# misc.net
KiCad netlist of a schematic drawn in Altium Designer
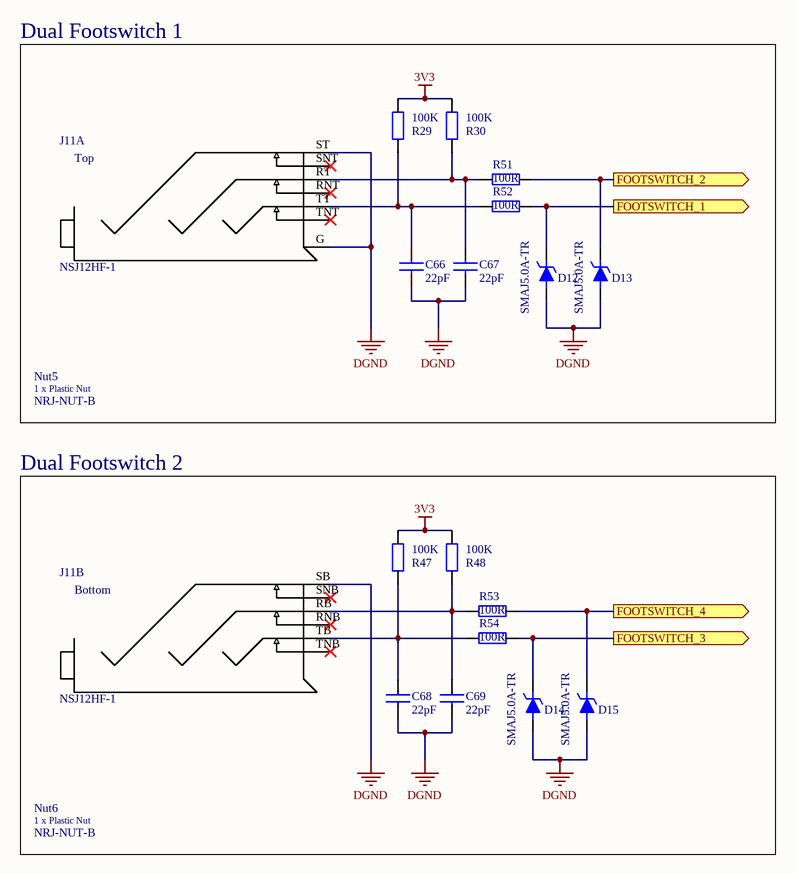
[diagram p0: misc.SchDoc]

(export (version "E")
  (design (tool "Eeschema 10.0.6"))
  (components
    (comp (ref "C66")
      (value "22pF")
      (footprint "SM/C_0603")
      (description "Capacitor, ceramic")
      (fields (field (name "MANUFACTURER") "Kemet ") (field (name "VOLTAGE") "50V"))
      (libsource (lib "Database_heig-vd") (part "Cap"))
    )
    (comp (ref "C67")
      (value "22pF")
      (footprint "SM/C_0603")
      (description "Capacitor, ceramic")
      (fields (field (name "MANUFACTURER") "Kemet ") (field (name "VOLTAGE") "50V"))
      (libsource (lib "Database_heig-vd") (part "Cap"))
    )
    (comp (ref "C68")
      (value "22pF")
      (footprint "SM/C_0603")
      (description "Capacitor, ceramic")
      (fields (field (name "MANUFACTURER") "Kemet ") (field (name "VOLTAGE") "50V"))
      (libsource (lib "Database_heig-vd") (part "Cap"))
    )
    (comp (ref "C69")
      (value "22pF")
      (footprint "SM/C_0603")
      (description "Capacitor, ceramic")
      (fields (field (name "MANUFACTURER") "Kemet ") (field (name "VOLTAGE") "50V"))
      (libsource (lib "Database_heig-vd") (part "Cap"))
    )
    (comp (ref "D12")
      (value "SMAJ5.0A-TR")
      (footprint "SM/D_DO214-AC (SMA)")
      (description "Transil™ diode")
      (fields (field (name "MANUFACTURER") "STMicroelectronics"))
      (libsource (lib "Database_heig-vd") (part "Diode TVS Unidirectional/A1C2"))
    )
    (comp (ref "D13")
      (value "SMAJ5.0A-TR")
      (footprint "SM/D_DO214-AC (SMA)")
      (description "Transil™ diode")
      (fields (field (name "MANUFACTURER") "STMicroelectronics"))
      (libsource (lib "Database_heig-vd") (part "Diode TVS Unidirectional/A1C2"))
    )
    (comp (ref "D14")
      (value "SMAJ5.0A-TR")
      (footprint "SM/D_DO214-AC (SMA)")
      (description "Transil™ diode")
      (fields (field (name "MANUFACTURER") "STMicroelectronics"))
      (libsource (lib "Database_heig-vd") (part "Diode TVS Unidirectional/A1C2"))
    )
    (comp (ref "D15")
      (value "SMAJ5.0A-TR")
      (footprint "SM/D_DO214-AC (SMA)")
      (description "Transil™ diode")
      (fields (field (name "MANUFACTURER") "STMicroelectronics"))
      (libsource (lib "Database_heig-vd") (part "Diode TVS Unidirectional/A1C2"))
    )
    (comp (ref "J11")
      (value "NSJ12HF-1")
      (footprint "NSJ12HF-1")
      (description "Neutronik 2xJack 6.35 connector")
      (libsource (lib "MBoard") (part "Jack 6.35 NSJ12HF-1"))
    )
    (comp (ref "Nut5")
      (value "NRJ-NUT-B")
      (description "Plastic Nut to fasten 6.35 jack")
      (fields (field (name "MANUFACTURER") "Neutrik"))
      (libsource (lib "MBoard") (part "Jack 6.35 Plastic Nut"))
    )
    (comp (ref "Nut6")
      (value "NRJ-NUT-B")
      (description "Plastic Nut to fasten 6.35 jack")
      (fields (field (name "MANUFACTURER") "Neutrik"))
      (libsource (lib "MBoard") (part "Jack 6.35 Plastic Nut"))
    )
    (comp (ref "R29")
      (value "100K")
      (footprint "SM/R_0603")
      (description "Résistance 0603 63mW 1% 100K")
      (fields (field (name "MANUFACTURER") "Multicomp") (field (name "POWER") "63mW"))
      (libsource (lib "Database_heig-vd") (part "Res"))
    )
    (comp (ref "R30")
      (value "100K")
      (footprint "SM/R_0603")
      (description "Résistance 0603 63mW 1% 100K")
      (fields (field (name "MANUFACTURER") "Multicomp") (field (name "POWER") "63mW"))
      (libsource (lib "Database_heig-vd") (part "Res"))
    )
    (comp (ref "R47")
      (value "100K")
      (footprint "SM/R_0603")
      (description "Résistance 0603 63mW 1% 100K")
      (fields (field (name "MANUFACTURER") "Multicomp") (field (name "POWER") "63mW"))
      (libsource (lib "Database_heig-vd") (part "Res"))
    )
    (comp (ref "R48")
      (value "100K")
      (footprint "SM/R_0603")
      (description "Résistance 0603 63mW 1% 100K")
      (fields (field (name "MANUFACTURER") "Multicomp") (field (name "POWER") "63mW"))
      (libsource (lib "Database_heig-vd") (part "Res"))
    )
    (comp (ref "R51")
      (value "100R")
      (footprint "SM/R_0603")
      (description "Résistance 0603 63mW 1% 100R")
      (fields (field (name "MANUFACTURER") "Multicomp") (field (name "POWER") "63mW"))
      (libsource (lib "Database_heig-vd") (part "Res"))
    )
    (comp (ref "R52")
      (value "100R")
      (footprint "SM/R_0603")
      (description "Résistance 0603 63mW 1% 100R")
      (fields (field (name "MANUFACTURER") "Multicomp") (field (name "POWER") "63mW"))
      (libsource (lib "Database_heig-vd") (part "Res"))
    )
    (comp (ref "R53")
      (value "100R")
      (footprint "SM/R_0603")
      (description "Résistance 0603 63mW 1% 100R")
      (fields (field (name "MANUFACTURER") "Multicomp") (field (name "POWER") "63mW"))
      (libsource (lib "Database_heig-vd") (part "Res"))
    )
    (comp (ref "R54")
      (value "100R")
      (footprint "SM/R_0603")
      (description "Résistance 0603 63mW 1% 100R")
      (fields (field (name "MANUFACTURER") "Multicomp") (field (name "POWER") "63mW"))
      (libsource (lib "Database_heig-vd") (part "Res"))
    )
  )
  (nets
    (net (code "1") (name "/FOOTSWITCH_1") (class "Default")
      (node (ref "D12") (pin "2") (pinfunction "C_2") (pintype "passive"))
      (node (ref "R52") (pin "2") (pinfunction "2_2") (pintype "passive"))
    )
    (net (code "2") (name "/FOOTSWITCH_2") (class "Default")
      (node (ref "D13") (pin "2") (pinfunction "C_2") (pintype "passive"))
      (node (ref "R51") (pin "2") (pinfunction "2_2") (pintype "passive"))
    )
    (net (code "3") (name "/FOOTSWITCH_3") (class "Default")
      (node (ref "D14") (pin "2") (pinfunction "C_2") (pintype "passive"))
      (node (ref "R54") (pin "2") (pinfunction "2_2") (pintype "passive"))
    )
    (net (code "4") (name "/FOOTSWITCH_4") (class "Default")
      (node (ref "D15") (pin "2") (pinfunction "C_2") (pintype "passive"))
      (node (ref "R53") (pin "2") (pinfunction "2_2") (pintype "passive"))
    )
    (net (code "5") (name "3V3") (class "Default")
      (node (ref "R29") (pin "1") (pinfunction "1_1") (pintype "passive"))
      (node (ref "R30") (pin "1") (pinfunction "1_1") (pintype "passive"))
      (node (ref "R47") (pin "1") (pinfunction "1_1") (pintype "passive"))
      (node (ref "R48") (pin "1") (pinfunction "1_1") (pintype "passive"))
    )
    (net (code "6") (name "DGND") (class "Default")
      (node (ref "C66") (pin "2") (pinfunction "2_2") (pintype "passive"))
      (node (ref "C67") (pin "2") (pinfunction "2_2") (pintype "passive"))
      (node (ref "C68") (pin "2") (pinfunction "2_2") (pintype "passive"))
      (node (ref "C69") (pin "2") (pinfunction "2_2") (pintype "passive"))
      (node (ref "D12") (pin "1") (pinfunction "A_1") (pintype "passive"))
      (node (ref "D13") (pin "1") (pinfunction "A_1") (pintype "passive"))
      (node (ref "D14") (pin "1") (pinfunction "A_1") (pintype "passive"))
      (node (ref "D15") (pin "1") (pinfunction "A_1") (pintype "passive"))
      (node (ref "J11") (pin "G") (pinfunction "G_G") (pintype "passive"))
      (node (ref "J11") (pin "SB") (pintype "passive"))
      (node (ref "J11") (pin "ST") (pintype "passive"))
    )
    (net (code "7") (name "Net-(C66-Pad1)") (class "Default")
      (node (ref "C66") (pin "1") (pinfunction "1_1") (pintype "passive"))
      (node (ref "J11") (pin "TT") (pintype "passive"))
      (node (ref "R29") (pin "2") (pinfunction "2_2") (pintype "passive"))
      (node (ref "R52") (pin "1") (pinfunction "1_1") (pintype "passive"))
    )
    (net (code "8") (name "Net-(C67-Pad1)") (class "Default")
      (node (ref "C67") (pin "1") (pinfunction "1_1") (pintype "passive"))
      (node (ref "J11") (pin "RT") (pintype "passive"))
      (node (ref "R30") (pin "2") (pinfunction "2_2") (pintype "passive"))
      (node (ref "R51") (pin "1") (pinfunction "1_1") (pintype "passive"))
    )
    (net (code "9") (name "Net-(C68-Pad1)") (class "Default")
      (node (ref "C68") (pin "1") (pinfunction "1_1") (pintype "passive"))
      (node (ref "J11") (pin "TB") (pintype "passive"))
      (node (ref "R47") (pin "2") (pinfunction "2_2") (pintype "passive"))
      (node (ref "R54") (pin "1") (pinfunction "1_1") (pintype "passive"))
    )
    (net (code "10") (name "Net-(C69-Pad1)") (class "Default")
      (node (ref "C69") (pin "1") (pinfunction "1_1") (pintype "passive"))
      (node (ref "J11") (pin "RB") (pintype "passive"))
      (node (ref "R48") (pin "2") (pinfunction "2_2") (pintype "passive"))
      (node (ref "R53") (pin "1") (pinfunction "1_1") (pintype "passive"))
    )
    (net (code "11") (name "unconnected-(J11-PadRNB)") (class "Default")
      (node (ref "J11") (pin "RNB") (pintype "passive+no_connect"))
    )
    (net (code "12") (name "unconnected-(J11-PadRNT)") (class "Default")
      (node (ref "J11") (pin "RNT") (pintype "passive+no_connect"))
    )
    (net (code "13") (name "unconnected-(J11-PadSNB)") (class "Default")
      (node (ref "J11") (pin "SNB") (pintype "passive+no_connect"))
    )
    (net (code "14") (name "unconnected-(J11-PadSNT)") (class "Default")
      (node (ref "J11") (pin "SNT") (pintype "passive+no_connect"))
    )
    (net (code "15") (name "unconnected-(J11-PadTNB)") (class "Default")
      (node (ref "J11") (pin "TNB") (pintype "passive+no_connect"))
    )
    (net (code "16") (name "unconnected-(J11-PadTNT)") (class "Default")
      (node (ref "J11") (pin "TNT") (pintype "passive+no_connect"))
    )
  )
)
